# RS232_NPN_PNP_Negative.net
KiCad netlist of a schematic drawn in EAGLE
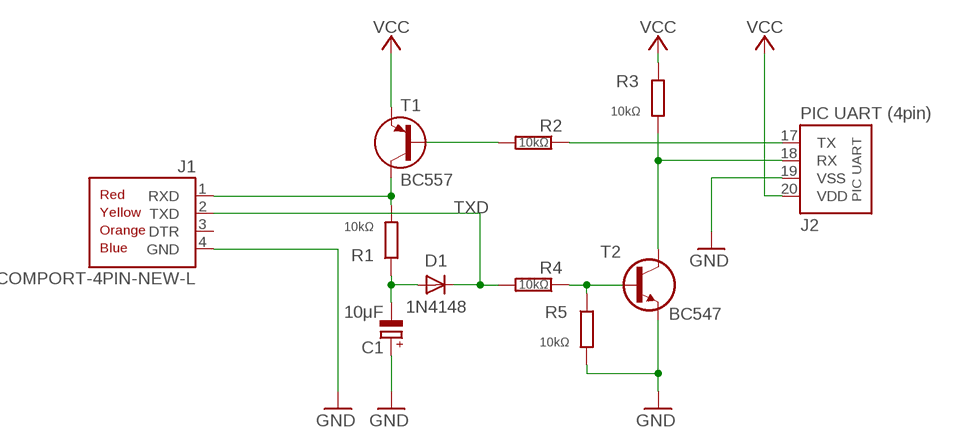
[diagram p0: schematic, sheet 1]

(export (version "E")
  (design (tool "Eeschema 10.0.6"))
  (components
    (comp (ref "C1")
      (value "10μF")
      (footprint "eagle-import:E2,5-3")
      (libsource (lib "eagle-import") (part "CPOLE2,5-3"))
    )
    (comp (ref "D1")
      (value "1N4148")
      (footprint "eagle-import:DO34-5")
      (libsource (lib "eagle-import") (part "1N414834-5"))
    )
    (comp (ref "J1")
      (value "COMPORT-4PIN-NEW-L")
      (footprint "eagle-import:RS232-4PIN-NEW-L")
      (libsource (lib "eagle-import") (part "COMPORT-4PIN-NEW-L"))
    )
    (comp (ref "J2")
      (value "PIC UART (4pin)")
      (footprint "eagle-import:PIC-UART")
      (libsource (lib "eagle-import") (part "PIC-UART"))
    )
    (comp (ref "R1")
      (value "10kΩ")
      (footprint "eagle-import:0202_7")
      (libsource (lib "eagle-import") (part "R0202/7"))
    )
    (comp (ref "R2")
      (value "10kΩ")
      (footprint "eagle-import:0202_10-V")
      (libsource (lib "eagle-import") (part "R0202/10-V"))
    )
    (comp (ref "R3")
      (value "10kΩ")
      (footprint "eagle-import:0202_7-V")
      (libsource (lib "eagle-import") (part "R0202/7-V"))
    )
    (comp (ref "R4")
      (value "10kΩ")
      (footprint "eagle-import:0202_7")
      (libsource (lib "eagle-import") (part "R0202/7"))
    )
    (comp (ref "R5")
      (value "10kΩ")
      (footprint "eagle-import:0202_7")
      (libsource (lib "eagle-import") (part "R0202/7"))
    )
    (comp (ref "T1")
      (value "BC557")
      (footprint "eagle-import:TO92-CBE")
      (libsource (lib "eagle-import") (part "BC557CBE"))
    )
    (comp (ref "T2")
      (value "BC547")
      (footprint "eagle-import:TO92-CBE")
      (libsource (lib "eagle-import") (part "BC547CBE"))
    )
  )
  (nets
    (net (code "1") (name "/TXD") (class "Default")
      (node (ref "D1") (pin "C") (pinfunction "C_C") (pintype "passive"))
      (node (ref "J1") (pin "2") (pinfunction "TXD_2") (pintype "passive"))
      (node (ref "R4") (pin "2") (pinfunction "2_2") (pintype "passive"))
    )
    (net (code "2") (name "GND") (class "Default")
      (node (ref "C1") (pin "+") (pinfunction "+_+") (pintype "passive"))
      (node (ref "J1") (pin "4") (pinfunction "GND_4") (pintype "passive"))
      (node (ref "J2") (pin "19") (pinfunction "VSS_19") (pintype "passive"))
      (node (ref "R5") (pin "2") (pinfunction "2_2") (pintype "passive"))
      (node (ref "T2") (pin "E") (pinfunction "E_E") (pintype "passive"))
    )
    (net (code "3") (name "Net-(C1-Pad-)") (class "Default")
      (node (ref "C1") (pin "-") (pinfunction "-_-") (pintype "passive"))
      (node (ref "D1") (pin "A") (pinfunction "A_A") (pintype "passive"))
      (node (ref "R1") (pin "1") (pinfunction "1_1") (pintype "passive"))
    )
    (net (code "4") (name "Net-(J1-RXD)") (class "Default")
      (node (ref "J1") (pin "1") (pinfunction "RXD_1") (pintype "passive"))
      (node (ref "R1") (pin "2") (pinfunction "2_2") (pintype "passive"))
      (node (ref "T1") (pin "C") (pinfunction "C_C") (pintype "passive"))
    )
    (net (code "5") (name "Net-(J2-RX)") (class "Default")
      (node (ref "J2") (pin "18") (pinfunction "RX_18") (pintype "passive"))
      (node (ref "R3") (pin "1") (pinfunction "1_1") (pintype "passive"))
      (node (ref "T2") (pin "C") (pinfunction "C_C") (pintype "passive"))
    )
    (net (code "6") (name "Net-(J2-TX)") (class "Default")
      (node (ref "J2") (pin "17") (pinfunction "TX_17") (pintype "passive"))
      (node (ref "R2") (pin "1") (pinfunction "1_1") (pintype "passive"))
    )
    (net (code "7") (name "Net-(R2-Pad2)") (class "Default")
      (node (ref "R2") (pin "2") (pinfunction "2_2") (pintype "passive"))
      (node (ref "T1") (pin "B") (pinfunction "B_B") (pintype "passive"))
    )
    (net (code "8") (name "Net-(R4-Pad1)") (class "Default")
      (node (ref "R4") (pin "1") (pinfunction "1_1") (pintype "passive"))
      (node (ref "R5") (pin "1") (pinfunction "1_1") (pintype "passive"))
      (node (ref "T2") (pin "B") (pinfunction "B_B") (pintype "passive"))
    )
    (net (code "9") (name "VCC") (class "Default")
      (node (ref "J2") (pin "20") (pinfunction "VDD_20") (pintype "passive"))
      (node (ref "R3") (pin "2") (pinfunction "2_2") (pintype "passive"))
      (node (ref "T1") (pin "E") (pinfunction "E_E") (pintype "passive"))
    )
    (net (code "10") (name "unconnected-(J1-DTR-Pad3)") (class "Default")
      (node (ref "J1") (pin "3") (pinfunction "DTR_3") (pintype "passive"))
    )
  )
)
